# CLK_GEN.net
KiCad netlist of a schematic drawn in Altium Designer
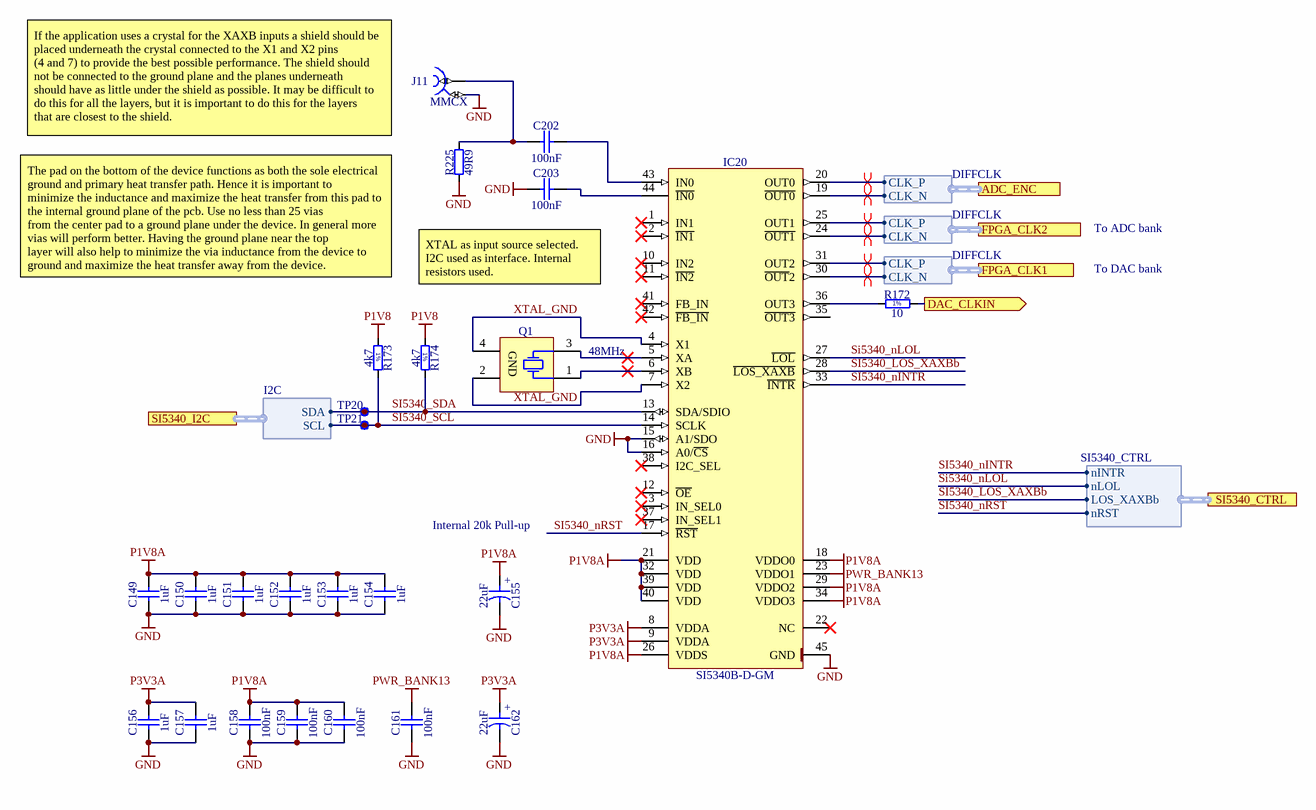
[diagram p0: CLK_GEN.SchDoc]

(export (version "E")
  (design (tool "Eeschema 10.0.6"))
  (components
    (comp (ref "C149")
      (value "1uF")
      (footprint "CAPC1005X55N")
      (description "Non-polarised capacitor")
      (fields
        (field (name "PART NUMBER") "CC0402_1UF_16V_10%_X5R")
        (field (name "VOLTAGE") "16V")
        (field (name "AUTHOR") "CERN DEM JLC")
      )
      (libsource (lib "Capacitors") (part "Capacitor - non polarized"))
    )
    (comp (ref "C150")
      (value "1uF")
      (footprint "CAPC1005X55N")
      (description "Non-polarised capacitor")
      (fields
        (field (name "PART NUMBER") "CC0402_1UF_16V_10%_X5R")
        (field (name "VOLTAGE") "16V")
        (field (name "AUTHOR") "CERN DEM JLC")
      )
      (libsource (lib "Capacitors") (part "Capacitor - non polarized"))
    )
    (comp (ref "C151")
      (value "1uF")
      (footprint "CAPC1005X55N")
      (description "Non-polarised capacitor")
      (fields
        (field (name "PART NUMBER") "CC0402_1UF_16V_10%_X5R")
        (field (name "VOLTAGE") "16V")
        (field (name "AUTHOR") "CERN DEM JLC")
      )
      (libsource (lib "Capacitors") (part "Capacitor - non polarized"))
    )
    (comp (ref "C152")
      (value "1uF")
      (footprint "CAPC1005X55N")
      (description "Non-polarised capacitor")
      (fields
        (field (name "PART NUMBER") "CC0402_1UF_16V_10%_X5R")
        (field (name "VOLTAGE") "16V")
        (field (name "AUTHOR") "CERN DEM JLC")
      )
      (libsource (lib "Capacitors") (part "Capacitor - non polarized"))
    )
    (comp (ref "C153")
      (value "1uF")
      (footprint "CAPC1005X55N")
      (description "Non-polarised capacitor")
      (fields
        (field (name "PART NUMBER") "CC0402_1UF_16V_10%_X5R")
        (field (name "VOLTAGE") "16V")
        (field (name "AUTHOR") "CERN DEM JLC")
      )
      (libsource (lib "Capacitors") (part "Capacitor - non polarized"))
    )
    (comp (ref "C154")
      (value "1uF")
      (footprint "CAPC1005X55N")
      (description "Non-polarised capacitor")
      (fields
        (field (name "PART NUMBER") "CC0402_1UF_16V_10%_X5R")
        (field (name "VOLTAGE") "16V")
        (field (name "AUTHOR") "CERN DEM JLC")
      )
      (libsource (lib "Capacitors") (part "Capacitor - non polarized"))
    )
    (comp (ref "C155")
      (value "22uF")
      (footprint "CAPMP3216X180N")
      (description "Polarised capacitor")
      (fields
        (field (name "PART NUMBER") "CTE3216-18_22UF_10V_10%")
        (field (name "VOLTAGE") "10V")
        (field (name "AUTHOR") "CERN DEM JLC")
      )
      (libsource (lib "Capacitors") (part "Capacitor - polarized"))
    )
    (comp (ref "C156")
      (value "1uF")
      (footprint "CAPC1005X55N")
      (description "Non-polarised capacitor")
      (fields
        (field (name "PART NUMBER") "CC0402_1UF_16V_10%_X5R")
        (field (name "VOLTAGE") "16V")
        (field (name "AUTHOR") "CERN DEM JLC")
      )
      (libsource (lib "Capacitors") (part "Capacitor - non polarized"))
    )
    (comp (ref "C157")
      (value "1uF")
      (footprint "CAPC1005X55N")
      (description "Non-polarised capacitor")
      (fields
        (field (name "PART NUMBER") "CC0402_1UF_16V_10%_X5R")
        (field (name "VOLTAGE") "16V")
        (field (name "AUTHOR") "CERN DEM JLC")
      )
      (libsource (lib "Capacitors") (part "Capacitor - non polarized"))
    )
    (comp (ref "C158")
      (value "100nF")
      (footprint "CAPC1005X55N")
      (description "Non-polarised capacitor")
      (fields
        (field (name "PART NUMBER") "CC0402_100NF_16V_10%_X5R")
        (field (name "VOLTAGE") "16V")
        (field (name "AUTHOR") "CERN DEM JLC")
      )
      (libsource (lib "Capacitors") (part "Capacitor - non polarized"))
    )
    (comp (ref "C159")
      (value "100nF")
      (footprint "CAPC1005X55N")
      (description "Non-polarised capacitor")
      (fields
        (field (name "PART NUMBER") "CC0402_100NF_16V_10%_X5R")
        (field (name "VOLTAGE") "16V")
        (field (name "AUTHOR") "CERN DEM JLC")
      )
      (libsource (lib "Capacitors") (part "Capacitor - non polarized"))
    )
    (comp (ref "C160")
      (value "100nF")
      (footprint "CAPC1005X55N")
      (description "Non-polarised capacitor")
      (fields
        (field (name "PART NUMBER") "CC0402_100NF_16V_10%_X5R")
        (field (name "VOLTAGE") "16V")
        (field (name "AUTHOR") "CERN DEM JLC")
      )
      (libsource (lib "Capacitors") (part "Capacitor - non polarized"))
    )
    (comp (ref "C161")
      (value "100nF")
      (footprint "CAPC1005X55N")
      (description "Non-polarised capacitor")
      (fields
        (field (name "PART NUMBER") "CC0402_100NF_16V_10%_X5R")
        (field (name "VOLTAGE") "16V")
        (field (name "AUTHOR") "CERN DEM JLC")
      )
      (libsource (lib "Capacitors") (part "Capacitor - non polarized"))
    )
    (comp (ref "C162")
      (value "22uF")
      (footprint "CAPMP3216X180N")
      (description "Polarised capacitor")
      (fields
        (field (name "PART NUMBER") "CTE3216-18_22UF_10V_10%")
        (field (name "VOLTAGE") "10V")
        (field (name "AUTHOR") "CERN DEM JLC")
      )
      (libsource (lib "Capacitors") (part "Capacitor - polarized"))
    )
    (comp (ref "C202")
      (value "100nF")
      (footprint "CAPC1005X55N")
      (description "Non-polarised capacitor")
      (fields
        (field (name "PART NUMBER") "CC0402_100NF_16V_10%_X5R")
        (field (name "VOLTAGE") "16V")
        (field (name "AUTHOR") "CERN DEM JLC")
      )
      (libsource (lib "Capacitors") (part "Capacitor - non polarized"))
    )
    (comp (ref "C203")
      (value "100nF")
      (footprint "CAPC1005X55N")
      (description "Non-polarised capacitor")
      (fields
        (field (name "PART NUMBER") "CC0402_100NF_16V_10%_X5R")
        (field (name "VOLTAGE") "16V")
        (field (name "AUTHOR") "CERN DEM JLC")
      )
      (libsource (lib "Capacitors") (part "Capacitor - non polarized"))
    )
    (comp (ref "IC20")
      (value "SI5340B-D-GM")
      (footprint "QFN50P700X700X90-45N-S530")
      (description "Low-Jitter, 10 or 4-Output, Any-Frequency, Any-Output Clock Generator")
      (fields (field (name "MANUFACTURER") "SILICON LABS") (field (name "AUTHOR") "CERN DEM JLC"))
      (libsource (lib "ICs And Semiconductors") (part "SI5340"))
    )
    (comp (ref "J11")
      (value "MMCX")
      (footprint "SAMTEC_MMCX-J-P-H-ST-TH1")
      (fields
        (field (name "PART NUMBER") "SAMTEC_MMCX-J-P-H-ST-TH1")
        (field (name "MANUFACTURER") "SAMTEC")
        (field (name "MANUFACTURER PART NUMBER") "MMCX-J-P-H-ST-TH1")
        (field (name "AUTHOR") "CERN DEM JLC")
      )
      (libsource (lib "Connectors") (part "Coax_1Female_1Shield"))
    )
    (comp (ref "Q1")
      (value "48MHz")
      (footprint "XTAL_TXC_7M")
      (description "Crystal 4 pins 1=XTAL Control 2=GND3=XTAL 4=GND")
      (fields
        (field (name "PART NUMBER") "XTAL_48MHZ_TXC_7M-48.000MAHV")
        (field (name "MANUFACTURER") "TXC CORPORATION")
        (field (name "AUTHOR") "CERN DEM MR")
      )
      (libsource (lib "ICs And Semiconductors") (part "Quartz Crystal 1X 2GND 3X 4GND"))
    )
    (comp (ref "R172")
      (value "10")
      (footprint "RESC1005X40N")
      (description "Resistor - 1%")
      (fields
        (field (name "PART NUMBER") "R0402_10R_1%_0.0625W_200PPM")
        (field (name "POWER") "0.0625W")
        (field (name "AUTHOR") "CERN DEM JLC")
      )
      (libsource (lib "Resistors") (part "Resistor - 1%"))
    )
    (comp (ref "R173")
      (value "4k7")
      (footprint "RESC1005X40N")
      (description "Resistor - 1%")
      (fields
        (field (name "PART NUMBER") "R0402_4K7_1%_0.0625W_100PPM")
        (field (name "POWER") "0.0625W")
        (field (name "AUTHOR") "CERN DEM JLC")
      )
      (libsource (lib "Resistors") (part "Resistor - 1%"))
    )
    (comp (ref "R174")
      (value "4k7")
      (footprint "RESC1005X40N")
      (description "Resistor - 1%")
      (fields
        (field (name "PART NUMBER") "R0402_4K7_1%_0.0625W_100PPM")
        (field (name "POWER") "0.0625W")
        (field (name "AUTHOR") "CERN DEM JLC")
      )
      (libsource (lib "Resistors") (part "Resistor - 1%"))
    )
    (comp (ref "R225")
      (value "49R9")
      (footprint "RESC1005X40N")
      (description "Resistor - 1%")
      (fields
        (field (name "PART NUMBER") "R0402_49R9_1%_0.0625W_100PPM")
        (field (name "POWER") "0.0625W")
        (field (name "AUTHOR") "CERN DEM JLC")
      )
      (libsource (lib "Resistors") (part "Resistor - 1%"))
    )
    (comp (ref "TP20")
      (value "SMD Pad")
      (footprint "C100")
      (description "Through Hole Pad")
      (fields (field (name "PART NUMBER") "SMD_PAD_D1MM") (field (name "AUTHOR") "CERN DEM JLC"))
      (libsource (lib "Eletro-mechanical") (part "Single SMD Pad (Round)"))
    )
    (comp (ref "TP21")
      (value "SMD Pad")
      (footprint "C100")
      (description "Through Hole Pad")
      (fields (field (name "PART NUMBER") "SMD_PAD_D1MM") (field (name "AUTHOR") "CERN DEM JLC"))
      (libsource (lib "Eletro-mechanical") (part "Single SMD Pad (Round)"))
    )
  )
  (nets
    (net (code "4") (name "/DAC_CLKIN") (class "Default")
      (node (ref "R172") (pin "2") (pinfunction "2_2") (pintype "passive"))
    )
    (net (code "5") (name "/SI5340_LOS_XAXBb") (class "Default")
      (node (ref "IC20") (pin "28") (pinfunction "~{LOS_XAXB}_28") (pintype "output"))
    )
    (net (code "6") (name "/SI5340_SCL") (class "Default")
      (node (ref "IC20") (pin "14") (pinfunction "SCLK_14") (pintype "input"))
      (node (ref "R173") (pin "2") (pinfunction "2_2") (pintype "passive"))
      (node (ref "TP21") (pin "1") (pinfunction "1_1") (pintype "bidirectional"))
    )
    (net (code "7") (name "/SI5340_SDA") (class "Default")
      (node (ref "IC20") (pin "13") (pinfunction "SDA/SDIO_13") (pintype "bidirectional"))
      (node (ref "R174") (pin "2") (pinfunction "2_2") (pintype "passive"))
      (node (ref "TP20") (pin "1") (pinfunction "1_1") (pintype "bidirectional"))
    )
    (net (code "8") (name "/SI5340_nINTR") (class "Default")
      (node (ref "IC20") (pin "33") (pinfunction "~{INTR}_33") (pintype "output"))
    )
    (net (code "9") (name "/SI5340_nRST") (class "Default")
      (node (ref "IC20") (pin "17") (pinfunction "~{RST}_17") (pintype "input"))
    )
    (net (code "10") (name "/Si5340_nLOL") (class "Default")
      (node (ref "IC20") (pin "27") (pinfunction "~{LOL}_27") (pintype "output"))
    )
    (net (code "11") (name "/XTAL_GND") (class "Default")
      (node (ref "IC20") (pin "4") (pinfunction "X1_4") (pintype "input"))
      (node (ref "IC20") (pin "7") (pinfunction "X2_7") (pintype "input"))
      (node (ref "Q1") (pin "2") (pinfunction "GND_2") (pintype "power_in"))
      (node (ref "Q1") (pin "4") (pinfunction "GND_4") (pintype "power_in"))
    )
    (net (code "15") (name "GND") (class "Default")
      (node (ref "C149") (pin "1") (pinfunction "1_1") (pintype "passive"))
      (node (ref "C150") (pin "1") (pinfunction "1_1") (pintype "passive"))
      (node (ref "C151") (pin "1") (pinfunction "1_1") (pintype "passive"))
      (node (ref "C152") (pin "1") (pinfunction "1_1") (pintype "passive"))
      (node (ref "C153") (pin "1") (pinfunction "1_1") (pintype "passive"))
      (node (ref "C154") (pin "1") (pinfunction "1_1") (pintype "passive"))
      (node (ref "C155") (pin "2") (pinfunction "2_2") (pintype "passive"))
      (node (ref "C156") (pin "1") (pinfunction "1_1") (pintype "passive"))
      (node (ref "C157") (pin "1") (pinfunction "1_1") (pintype "passive"))
      (node (ref "C158") (pin "1") (pinfunction "1_1") (pintype "passive"))
      (node (ref "C159") (pin "1") (pinfunction "1_1") (pintype "passive"))
      (node (ref "C160") (pin "1") (pinfunction "1_1") (pintype "passive"))
      (node (ref "C161") (pin "1") (pinfunction "1_1") (pintype "passive"))
      (node (ref "C162") (pin "2") (pinfunction "2_2") (pintype "passive"))
      (node (ref "C203") (pin "1") (pinfunction "1_1") (pintype "passive"))
      (node (ref "IC20") (pin "15") (pinfunction "A1/SDO_15") (pintype "bidirectional"))
      (node (ref "IC20") (pin "16") (pinfunction "A0/~{CS}_16") (pintype "input"))
      (node (ref "IC20") (pin "45") (pinfunction "GND_45") (pintype "power_in"))
      (node (ref "J11") (pin "2") (pinfunction "2_2") (pintype "bidirectional"))
      (node (ref "R225") (pin "1") (pinfunction "1_1") (pintype "passive"))
    )
    (net (code "16") (name "Net-(C202-Pad1)") (class "Default")
      (node (ref "C202") (pin "1") (pinfunction "1_1") (pintype "passive"))
      (node (ref "J11") (pin "1") (pinfunction "1_1") (pintype "bidirectional"))
      (node (ref "R225") (pin "2") (pinfunction "2_2") (pintype "passive"))
    )
    (net (code "17") (name "Net-(IC20-IN0)") (class "Default")
      (node (ref "C202") (pin "2") (pinfunction "2_2") (pintype "passive"))
      (node (ref "IC20") (pin "43") (pinfunction "IN0_43") (pintype "input"))
    )
    (net (code "18") (name "Net-(IC20-OUT3)") (class "Default")
      (node (ref "IC20") (pin "36") (pinfunction "OUT3_36") (pintype "output"))
      (node (ref "R172") (pin "1") (pinfunction "1_1") (pintype "passive"))
    )
    (net (code "19") (name "Net-(IC20-XA)") (class "Default")
      (node (ref "IC20") (pin "5") (pinfunction "XA_5") (pintype "input"))
      (node (ref "Q1") (pin "3") (pinfunction "X_3") (pintype "passive"))
    )
    (net (code "20") (name "Net-(IC20-XB)") (class "Default")
      (node (ref "IC20") (pin "6") (pinfunction "XB_6") (pintype "input"))
      (node (ref "Q1") (pin "1") (pinfunction "X_1") (pintype "passive"))
    )
    (net (code "21") (name "Net-(IC20-~{IN0})") (class "Default")
      (node (ref "C203") (pin "2") (pinfunction "2_2") (pintype "passive"))
      (node (ref "IC20") (pin "44") (pinfunction "~{IN0}_44") (pintype "open_collector"))
    )
    (net (code "22") (name "P1V8") (class "Default")
      (node (ref "R173") (pin "1") (pinfunction "1_1") (pintype "passive"))
      (node (ref "R174") (pin "1") (pinfunction "1_1") (pintype "passive"))
    )
    (net (code "23") (name "P1V8A") (class "Default")
      (node (ref "C149") (pin "2") (pinfunction "2_2") (pintype "passive"))
      (node (ref "C150") (pin "2") (pinfunction "2_2") (pintype "passive"))
      (node (ref "C151") (pin "2") (pinfunction "2_2") (pintype "passive"))
      (node (ref "C152") (pin "2") (pinfunction "2_2") (pintype "passive"))
      (node (ref "C153") (pin "2") (pinfunction "2_2") (pintype "passive"))
      (node (ref "C154") (pin "2") (pinfunction "2_2") (pintype "passive"))
      (node (ref "C155") (pin "1") (pinfunction "1_1") (pintype "passive"))
      (node (ref "C158") (pin "2") (pinfunction "2_2") (pintype "passive"))
      (node (ref "C159") (pin "2") (pinfunction "2_2") (pintype "passive"))
      (node (ref "C160") (pin "2") (pinfunction "2_2") (pintype "passive"))
      (node (ref "IC20") (pin "18") (pinfunction "VDDO0_18") (pintype "power_in"))
      (node (ref "IC20") (pin "21") (pinfunction "VDD_21") (pintype "power_in"))
      (node (ref "IC20") (pin "26") (pinfunction "VDDS_26") (pintype "power_in"))
      (node (ref "IC20") (pin "29") (pinfunction "VDDO2_29") (pintype "power_in"))
      (node (ref "IC20") (pin "32") (pinfunction "VDD_32") (pintype "power_in"))
      (node (ref "IC20") (pin "34") (pinfunction "VDDO3_34") (pintype "power_in"))
      (node (ref "IC20") (pin "39") (pinfunction "VDD_39") (pintype "power_in"))
      (node (ref "IC20") (pin "40") (pinfunction "VDD_40") (pintype "power_in"))
    )
    (net (code "24") (name "P3V3A") (class "Default")
      (node (ref "C156") (pin "2") (pinfunction "2_2") (pintype "passive"))
      (node (ref "C157") (pin "2") (pinfunction "2_2") (pintype "passive"))
      (node (ref "C162") (pin "1") (pinfunction "1_1") (pintype "passive"))
      (node (ref "IC20") (pin "8") (pinfunction "VDDA_8") (pintype "power_in"))
      (node (ref "IC20") (pin "9") (pinfunction "VDDA_9") (pintype "power_in"))
    )
    (net (code "25") (name "PWR_BANK13") (class "Default")
      (node (ref "C161") (pin "2") (pinfunction "2_2") (pintype "passive"))
      (node (ref "IC20") (pin "23") (pinfunction "VDDO1_23") (pintype "power_in"))
    )
    (net (code "26") (name "unconnected-(IC20-FB_IN-Pad41)") (class "Default")
      (node (ref "IC20") (pin "41") (pinfunction "FB_IN_41") (pintype "input+no_connect"))
    )
    (net (code "27") (name "unconnected-(IC20-I2C_SEL-Pad38)") (class "Default")
      (node (ref "IC20") (pin "38") (pinfunction "I2C_SEL_38") (pintype "input+no_connect"))
    )
    (net (code "28") (name "unconnected-(IC20-IN1-Pad1)") (class "Default")
      (node (ref "IC20") (pin "1") (pinfunction "IN1_1") (pintype "input+no_connect"))
    )
    (net (code "29") (name "unconnected-(IC20-IN2-Pad10)") (class "Default")
      (node (ref "IC20") (pin "10") (pinfunction "IN2_10") (pintype "input+no_connect"))
    )
    (net (code "30") (name "unconnected-(IC20-IN_SEL0-Pad3)") (class "Default")
      (node (ref "IC20") (pin "3") (pinfunction "IN_SEL0_3") (pintype "input+no_connect"))
    )
    (net (code "31") (name "unconnected-(IC20-IN_SEL1-Pad37)") (class "Default")
      (node (ref "IC20") (pin "37") (pinfunction "IN_SEL1_37") (pintype "input+no_connect"))
    )
    (net (code "32") (name "unconnected-(IC20-NC-Pad22)") (class "Default")
      (node (ref "IC20") (pin "22") (pinfunction "NC_22") (pintype "passive+no_connect"))
    )
    (net (code "33") (name "unconnected-(IC20-OUT0-Pad20)") (class "Default")
      (node (ref "IC20") (pin "20") (pinfunction "OUT0_20") (pintype "output"))
    )
    (net (code "34") (name "unconnected-(IC20-OUT1-Pad25)") (class "Default")
      (node (ref "IC20") (pin "25") (pinfunction "OUT1_25") (pintype "output"))
    )
    (net (code "35") (name "unconnected-(IC20-OUT2-Pad31)") (class "Default")
      (node (ref "IC20") (pin "31") (pinfunction "OUT2_31") (pintype "output"))
    )
    (net (code "36") (name "unconnected-(IC20-~{FB_IN}-Pad42)") (class "Default")
      (node (ref "IC20") (pin "42") (pinfunction "~{FB_IN}_42") (pintype "input+no_connect"))
    )
    (net (code "37") (name "unconnected-(IC20-~{IN1}-Pad2)") (class "Default")
      (node (ref "IC20") (pin "2") (pinfunction "~{IN1}_2") (pintype "input+no_connect"))
    )
    (net (code "38") (name "unconnected-(IC20-~{IN2}-Pad11)") (class "Default")
      (node (ref "IC20") (pin "11") (pinfunction "~{IN2}_11") (pintype "input+no_connect"))
    )
    (net (code "39") (name "unconnected-(IC20-~{OE}-Pad12)") (class "Default")
      (node (ref "IC20") (pin "12") (pinfunction "~{OE}_12") (pintype "input+no_connect"))
    )
    (net (code "40") (name "unconnected-(IC20-~{OUT0}-Pad19)") (class "Default")
      (node (ref "IC20") (pin "19") (pinfunction "~{OUT0}_19") (pintype "output"))
    )
    (net (code "41") (name "unconnected-(IC20-~{OUT1}-Pad24)") (class "Default")
      (node (ref "IC20") (pin "24") (pinfunction "~{OUT1}_24") (pintype "output"))
    )
    (net (code "42") (name "unconnected-(IC20-~{OUT3}-Pad35)") (class "Default")
      (node (ref "IC20") (pin "35") (pinfunction "~{OUT3}_35") (pintype "output"))
    )
    (net (code "43") (name "unconnected-(IC20-~{OUT}2-Pad30)") (class "Default")
      (node (ref "IC20") (pin "30") (pinfunction "~{OUT}2_30") (pintype "output"))
    )
  )
)
